# CoffeeCounter.net
KiCad netlist of a schematic drawn in EAGLE
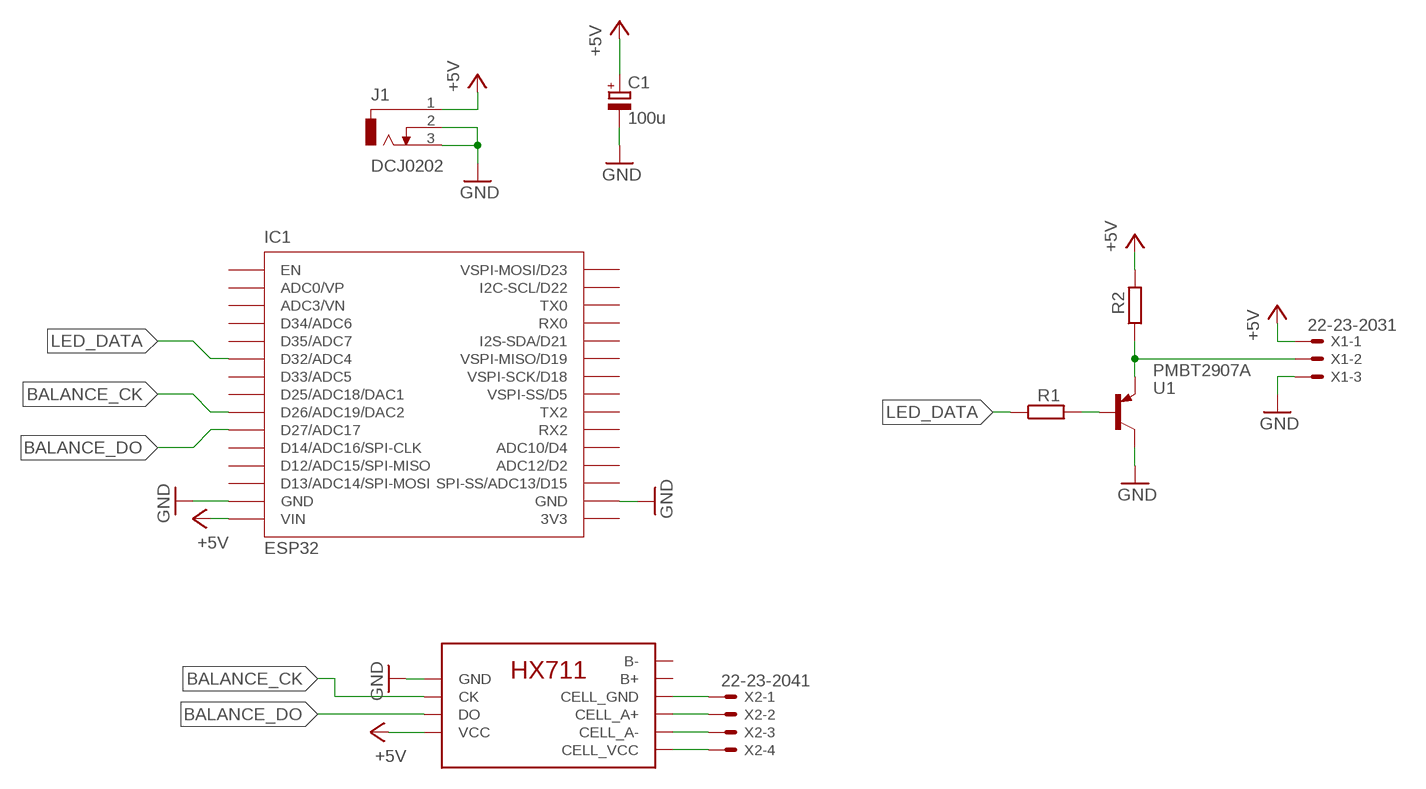
[diagram p0: schematic, sheet 1]

(export (version "E")
  (design (tool "Eeschema 10.0.6"))
  (components
    (comp (ref "C1")
      (value "100u")
      (footprint "eagle-import:E3,5-8")
      (libsource (lib "eagle-import") (part "CPOL-EUE3.5-8"))
    )
    (comp (ref "IC1")
      (value "ESP32")
      (footprint "eagle-import:ESP32")
      (libsource (lib "eagle-import") (part "ESP32"))
    )
    (comp (ref "J1")
      (value "DCJ0202")
      (footprint "eagle-import:DCJ0202")
      (libsource (lib "eagle-import") (part "DCJ0202"))
    )
    (comp (ref "R1")
      (value "R-EU_R0603")
      (footprint "eagle-import:R0603")
      (libsource (lib "eagle-import") (part "R-EU_R0603"))
    )
    (comp (ref "R2")
      (value "R-EU_R0603")
      (footprint "eagle-import:R0603")
      (libsource (lib "eagle-import") (part "R-EU_R0603"))
    )
    (comp (ref "U$1")
      (value "HX711_BREAKOUT")
      (footprint "eagle-import:HX711_BREAKOUT")
      (libsource (lib "eagle-import") (part "HX711_BREAKOUT"))
    )
    (comp (ref "U1")
      (value "PMBT2907A")
      (footprint "eagle-import:SOT23_NEX")
      (fields (field (name "COPYRIGHT") "Copyright (C) 2016 Accelerated Designs. All rights reserved"))
      (libsource (lib "eagle-import") (part "PMBT2907A"))
    )
    (comp (ref "X1")
      (value "22-23-2031")
      (footprint "eagle-import:22-23-2031")
      (fields (field (name "MF") "MOLEX"))
      (libsource (lib "eagle-import") (part "22-23-2031"))
    )
    (comp (ref "X2")
      (value "22-23-2041")
      (footprint "eagle-import:22-23-2041")
      (fields (field (name "MF") "MOLEX"))
      (libsource (lib "eagle-import") (part "22-23-2041"))
    )
  )
  (nets
    (net (code "1") (name "+5V") (class "Default")
      (node (ref "C1") (pin "+") (pinfunction "+_+") (pintype "passive"))
      (node (ref "IC1") (pin "VIN") (pinfunction "VIN_VIN") (pintype "power_in"))
      (node (ref "J1") (pin "1") (pinfunction "1_1") (pintype "passive"))
      (node (ref "R2") (pin "2") (pinfunction "2_2") (pintype "passive"))
      (node (ref "U$1") (pin "VCC") (pinfunction "VCC_VCC") (pintype "passive"))
      (node (ref "X1") (pin "1") (pinfunction "S_1") (pintype "passive"))
    )
    (net (code "2") (name "/3V3") (class "Default")
      (node (ref "IC1") (pin "3V3") (pinfunction "3V3_3V3") (pintype "power_in"))
    )
    (net (code "3") (name "/ADC3{slash}VN") (class "Default")
      (node (ref "IC1") (pin "VN") (pinfunction "ADC3/VN_VN") (pintype "power_in"))
    )
    (net (code "4") (name "/D13{slash}ADC14{slash}SPI-MOSI") (class "Default")
      (node (ref "IC1") (pin "D13") (pinfunction "D13/ADC14/SPI-MOSI_D13") (pintype "power_in"))
    )
    (net (code "5") (name "BALANCE_CK") (class "Default")
      (node (ref "IC1") (pin "D26") (pinfunction "D26/ADC19/DAC2_D26") (pintype "bidirectional"))
      (node (ref "U$1") (pin "CK") (pinfunction "CK_CK") (pintype "passive"))
    )
    (net (code "6") (name "BALANCE_DO") (class "Default")
      (node (ref "IC1") (pin "D27") (pinfunction "D27/ADC17_D27") (pintype "bidirectional"))
      (node (ref "U$1") (pin "DO") (pinfunction "DO_DO") (pintype "passive"))
    )
    (net (code "7") (name "GND") (class "Default")
      (node (ref "C1") (pin "-") (pinfunction "-_-") (pintype "passive"))
      (node (ref "IC1") (pin "GND@1") (pinfunction "GND_GND@1") (pintype "power_in"))
      (node (ref "IC1") (pin "GND@2") (pinfunction "GND_GND@2") (pintype "power_in"))
      (node (ref "J1") (pin "2") (pinfunction "2_2") (pintype "passive"))
      (node (ref "J1") (pin "3") (pinfunction "3_3") (pintype "passive"))
      (node (ref "U$1") (pin "GND") (pinfunction "GND_GND") (pintype "passive"))
      (node (ref "U1") (pin "3") (pinfunction "C_3") (pintype "passive"))
      (node (ref "X1") (pin "3") (pinfunction "S_3") (pintype "passive"))
    )
    (net (code "8") (name "LED_DATA") (class "Default")
      (node (ref "IC1") (pin "D32") (pinfunction "D32/ADC4_D32") (pintype "power_in"))
      (node (ref "R1") (pin "1") (pinfunction "1_1") (pintype "passive"))
    )
    (net (code "9") (name "Net-(U$1-CELL_VCC)") (class "Default")
      (node (ref "U$1") (pin "CELL_OUT+") (pinfunction "CELL_VCC_CELL_OUT+") (pintype "passive"))
      (node (ref "X2") (pin "4") (pinfunction "S_4") (pintype "passive"))
    )
    (net (code "10") (name "Net-(U1-B)") (class "Default")
      (node (ref "R1") (pin "2") (pinfunction "2_2") (pintype "passive"))
      (node (ref "U1") (pin "1") (pinfunction "B_1") (pintype "passive"))
    )
    (net (code "11") (name "Net-(U1-E)") (class "Default")
      (node (ref "R2") (pin "1") (pinfunction "1_1") (pintype "passive"))
      (node (ref "U1") (pin "2") (pinfunction "E_2") (pintype "passive"))
      (node (ref "X1") (pin "2") (pinfunction "S_2") (pintype "passive"))
    )
    (net (code "12") (name "Net-(X2A-S)") (class "Default")
      (node (ref "U$1") (pin "CELL_GND") (pinfunction "CELL_GND_CELL_GND") (pintype "passive"))
      (node (ref "X2") (pin "1") (pinfunction "S_1") (pintype "passive"))
    )
    (net (code "13") (name "Net-(X2B-S)") (class "Default")
      (node (ref "U$1") (pin "CELL_A+") (pinfunction "CELL_A+_CELL_A+") (pintype "passive"))
      (node (ref "X2") (pin "2") (pinfunction "S_2") (pintype "passive"))
    )
    (net (code "14") (name "Net-(X2C-S)") (class "Default")
      (node (ref "U$1") (pin "CELL_A-") (pinfunction "CELL_A-_CELL_A-") (pintype "passive"))
      (node (ref "X2") (pin "3") (pinfunction "S_3") (pintype "passive"))
    )
    (net (code "15") (name "unconnected-(IC1-ADC0{slash}VP-PadVP)") (class "Default")
      (node (ref "IC1") (pin "VP") (pinfunction "ADC0/VP_VP") (pintype "bidirectional"))
    )
    (net (code "16") (name "unconnected-(IC1-ADC10{slash}D4-PadD4)") (class "Default")
      (node (ref "IC1") (pin "D4") (pinfunction "ADC10/D4_D4") (pintype "bidirectional"))
    )
    (net (code "17") (name "unconnected-(IC1-ADC12{slash}D2-PadD2)") (class "Default")
      (node (ref "IC1") (pin "D2") (pinfunction "ADC12/D2_D2") (pintype "bidirectional"))
    )
    (net (code "18") (name "unconnected-(IC1-D12{slash}ADC15{slash}SPI-MISO-PadD12)") (class "Default")
      (node (ref "IC1") (pin "D12") (pinfunction "D12/ADC15/SPI-MISO_D12") (pintype "bidirectional"))
    )
    (net (code "19") (name "unconnected-(IC1-D14{slash}ADC16{slash}SPI-CLK-PadD14)") (class "Default")
      (node (ref "IC1") (pin "D14") (pinfunction "D14/ADC16/SPI-CLK_D14") (pintype "bidirectional"))
    )
    (net (code "20") (name "unconnected-(IC1-D25{slash}ADC18{slash}DAC1-PadD25)") (class "Default")
      (node (ref "IC1") (pin "D25") (pinfunction "D25/ADC18/DAC1_D25") (pintype "bidirectional"))
    )
    (net (code "21") (name "unconnected-(IC1-D33{slash}ADC5-PadD33)") (class "Default")
      (node (ref "IC1") (pin "D33") (pinfunction "D33/ADC5_D33") (pintype "bidirectional"))
    )
    (net (code "22") (name "unconnected-(IC1-D34{slash}ADC6-PadD34)") (class "Default")
      (node (ref "IC1") (pin "D34") (pinfunction "D34/ADC6_D34") (pintype "bidirectional"))
    )
    (net (code "23") (name "unconnected-(IC1-D35{slash}ADC7-PadD35)") (class "Default")
      (node (ref "IC1") (pin "D35") (pinfunction "D35/ADC7_D35") (pintype "bidirectional"))
    )
    (net (code "24") (name "unconnected-(IC1-I2C-SCL{slash}D22-PadD22)") (class "Default")
      (node (ref "IC1") (pin "D22") (pinfunction "I2C-SCL/D22_D22") (pintype "bidirectional"))
    )
    (net (code "25") (name "unconnected-(IC1-I2S-SDA{slash}D21-PadD21)") (class "Default")
      (node (ref "IC1") (pin "D21") (pinfunction "I2S-SDA/D21_D21") (pintype "bidirectional"))
    )
    (net (code "26") (name "unconnected-(IC1-PadEN)") (class "Default")
      (node (ref "IC1") (pin "EN") (pinfunction "EN_EN") (pintype "bidirectional"))
    )
    (net (code "27") (name "unconnected-(IC1-PadRX0)") (class "Default")
      (node (ref "IC1") (pin "RX0") (pinfunction "RX0_RX0") (pintype "bidirectional"))
    )
    (net (code "28") (name "unconnected-(IC1-PadRX2)") (class "Default")
      (node (ref "IC1") (pin "RX2") (pinfunction "RX2_RX2") (pintype "bidirectional"))
    )
    (net (code "29") (name "unconnected-(IC1-PadTX0)") (class "Default")
      (node (ref "IC1") (pin "TX0") (pinfunction "TX0_TX0") (pintype "bidirectional"))
    )
    (net (code "30") (name "unconnected-(IC1-PadTX2)") (class "Default")
      (node (ref "IC1") (pin "TX2") (pinfunction "TX2_TX2") (pintype "bidirectional"))
    )
    (net (code "31") (name "unconnected-(IC1-SPI-SS{slash}ADC13{slash}D15-PadD15)") (class "Default")
      (node (ref "IC1") (pin "D15") (pinfunction "SPI-SS/ADC13/D15_D15") (pintype "bidirectional"))
    )
    (net (code "32") (name "unconnected-(IC1-VSPI-MISO{slash}D19-PadD19)") (class "Default")
      (node (ref "IC1") (pin "D19") (pinfunction "VSPI-MISO/D19_D19") (pintype "bidirectional"))
    )
    (net (code "33") (name "unconnected-(IC1-VSPI-MOSI{slash}D23-PadD23)") (class "Default")
      (node (ref "IC1") (pin "D23") (pinfunction "VSPI-MOSI/D23_D23") (pintype "bidirectional"))
    )
    (net (code "34") (name "unconnected-(IC1-VSPI-SCK{slash}D18-PadD18)") (class "Default")
      (node (ref "IC1") (pin "D18") (pinfunction "VSPI-SCK/D18_D18") (pintype "bidirectional"))
    )
    (net (code "35") (name "unconnected-(IC1-VSPI-SS{slash}D5-PadD5)") (class "Default")
      (node (ref "IC1") (pin "D5") (pinfunction "VSPI-SS/D5_D5") (pintype "bidirectional"))
    )
    (net (code "36") (name "unconnected-(U$1-PadB+)") (class "Default")
      (node (ref "U$1") (pin "B+") (pinfunction "B+_B+") (pintype "passive"))
    )
    (net (code "37") (name "unconnected-(U$1-PadB-)") (class "Default")
      (node (ref "U$1") (pin "B-") (pinfunction "B-_B-") (pintype "passive"))
    )
  )
)
